# ESP8266-03-Switch.net
KiCad netlist of a schematic drawn in EAGLE
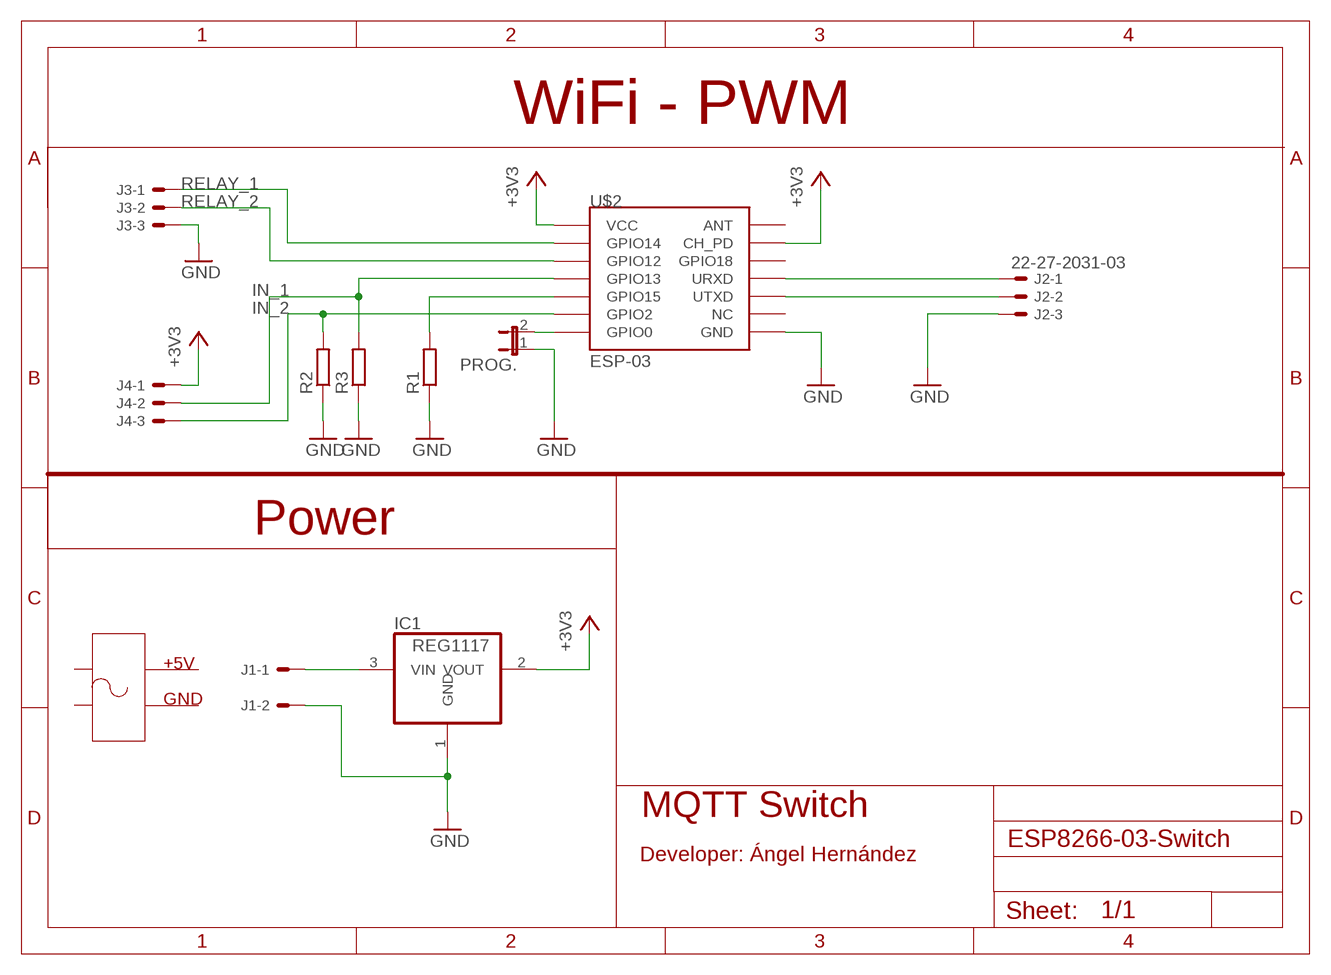
[diagram p0: schematic, sheet 1]

(export (version "E")
  (design (tool "Eeschema 10.0.6"))
  (components
    (comp (ref "IC1")
      (value "REG1117")
      (footprint "eagle-import:SOT223")
      (libsource (lib "eagle-import") (part "REG1117"))
    )
    (comp (ref "J1")
      (value "22-27-2021-02")
      (footprint "eagle-import:6410-02")
      (libsource (lib "eagle-import") (part "22-?-0227-2021"))
    )
    (comp (ref "J2")
      (value "22-27-2031-03")
      (footprint "eagle-import:6410-03")
      (libsource (lib "eagle-import") (part "22-?-0327-2031"))
    )
    (comp (ref "J3")
      (value "22-27-2031-03")
      (footprint "eagle-import:6410-03")
      (fields (field (name "OC_FARNELL") "unknown") (field (name "OC_NEWARK") "unknown"))
      (libsource (lib "eagle-import") (part "22-?-0327-2031"))
    )
    (comp (ref "J4")
      (value "22-27-2031-03")
      (footprint "eagle-import:6410-03")
      (fields (field (name "OC_FARNELL") "unknown") (field (name "OC_NEWARK") "unknown"))
      (libsource (lib "eagle-import") (part "22-?-0327-2031"))
    )
    (comp (ref "PROG.")
      (value "JP1E")
      (footprint "eagle-import:JP1")
      (libsource (lib "eagle-import") (part "JP1E"))
    )
    (comp (ref "R1")
      (value "R-EU_0204/7")
      (footprint "eagle-import:0204_7")
      (libsource (lib "eagle-import") (part "R-EU_0204/7"))
    )
    (comp (ref "R2")
      (value "R-EU_0204/7")
      (footprint "eagle-import:0204_7")
      (libsource (lib "eagle-import") (part "R-EU_0204/7"))
    )
    (comp (ref "R3")
      (value "R-EU_0204/7")
      (footprint "eagle-import:0204_7")
      (libsource (lib "eagle-import") (part "R-EU_0204/7"))
    )
    (comp (ref "U$2")
      (value "ESP-03")
      (footprint "eagle-import:ESP-03")
      (libsource (lib "eagle-import") (part "ESP-03"))
    )
  )
  (nets
    (net (code "1") (name "+3V3") (class "Default")
      (node (ref "IC1") (pin "2") (pinfunction "VOUT_2") (pintype "output"))
      (node (ref "J4") (pin "1") (pinfunction "S_1") (pintype "passive"))
      (node (ref "U$2") (pin "CH_PD") (pinfunction "CH_PD_CH_PD") (pintype "bidirectional"))
      (node (ref "U$2") (pin "VCC") (pinfunction "VCC_VCC") (pintype "bidirectional"))
    )
    (net (code "2") (name "/IN_1") (class "Default")
      (node (ref "J4") (pin "2") (pinfunction "S_2") (pintype "passive"))
      (node (ref "R3") (pin "2") (pinfunction "2_2") (pintype "passive"))
      (node (ref "U$2") (pin "GPIO13") (pinfunction "GPIO13_GPIO13") (pintype "bidirectional"))
    )
    (net (code "3") (name "/IN_2") (class "Default")
      (node (ref "J4") (pin "3") (pinfunction "S_3") (pintype "passive"))
      (node (ref "R2") (pin "2") (pinfunction "2_2") (pintype "passive"))
      (node (ref "U$2") (pin "GPIO2") (pinfunction "GPIO2_GPIO2") (pintype "bidirectional"))
    )
    (net (code "4") (name "/RELAY_1") (class "Default")
      (node (ref "J3") (pin "1") (pinfunction "S_1") (pintype "passive"))
      (node (ref "U$2") (pin "GPIO14") (pinfunction "GPIO14_GPIO14") (pintype "bidirectional"))
    )
    (net (code "5") (name "/RELAY_2") (class "Default")
      (node (ref "J3") (pin "2") (pinfunction "S_2") (pintype "passive"))
      (node (ref "U$2") (pin "GPIO12") (pinfunction "GPIO12_GPIO12") (pintype "bidirectional"))
    )
    (net (code "6") (name "GND") (class "Default")
      (node (ref "IC1") (pin "1") (pinfunction "GND_1") (pintype "power_in"))
      (node (ref "J1") (pin "2") (pinfunction "S_2") (pintype "passive"))
      (node (ref "J2") (pin "3") (pinfunction "S_3") (pintype "passive"))
      (node (ref "J3") (pin "3") (pinfunction "S_3") (pintype "passive"))
      (node (ref "PROG.") (pin "1") (pinfunction "1_1") (pintype "passive"))
      (node (ref "R1") (pin "1") (pinfunction "1_1") (pintype "passive"))
      (node (ref "R2") (pin "1") (pinfunction "1_1") (pintype "passive"))
      (node (ref "R3") (pin "1") (pinfunction "1_1") (pintype "passive"))
      (node (ref "U$2") (pin "GND") (pinfunction "GND_GND") (pintype "bidirectional"))
    )
    (net (code "7") (name "Net-(IC1-VIN)") (class "Default")
      (node (ref "IC1") (pin "3") (pinfunction "VIN_3") (pintype "input"))
      (node (ref "J1") (pin "1") (pinfunction "S_1") (pintype "passive"))
    )
    (net (code "8") (name "Net-(J2A-S)") (class "Default")
      (node (ref "J2") (pin "1") (pinfunction "S_1") (pintype "passive"))
      (node (ref "U$2") (pin "URXD") (pinfunction "URXD_URXD") (pintype "bidirectional"))
    )
    (net (code "9") (name "Net-(J2B-S)") (class "Default")
      (node (ref "J2") (pin "2") (pinfunction "S_2") (pintype "passive"))
      (node (ref "U$2") (pin "UTXD") (pinfunction "UTXD_UTXD") (pintype "bidirectional"))
    )
    (net (code "10") (name "Net-(PROG.-Pad2)") (class "Default")
      (node (ref "PROG.") (pin "2") (pinfunction "2_2") (pintype "passive"))
      (node (ref "U$2") (pin "GPIO0") (pinfunction "GPIO0_GPIO0") (pintype "bidirectional"))
    )
    (net (code "11") (name "Net-(R1-Pad2)") (class "Default")
      (node (ref "R1") (pin "2") (pinfunction "2_2") (pintype "passive"))
      (node (ref "U$2") (pin "GPIO15") (pinfunction "GPIO15_GPIO15") (pintype "bidirectional"))
    )
    (net (code "12") (name "unconnected-(U$2-PadANT)") (class "Default")
      (node (ref "U$2") (pin "ANT") (pinfunction "ANT_ANT") (pintype "bidirectional"))
    )
    (net (code "13") (name "unconnected-(U$2-PadGPIO18)") (class "Default")
      (node (ref "U$2") (pin "GPIO18") (pinfunction "GPIO18_GPIO18") (pintype "bidirectional"))
    )
    (net (code "14") (name "unconnected-(U$2-PadNC)") (class "Default")
      (node (ref "U$2") (pin "NC") (pinfunction "NC_NC") (pintype "bidirectional"))
    )
  )
)
